# LiPo_Drop_Charger.net
KiCad netlist of a schematic drawn in EAGLE
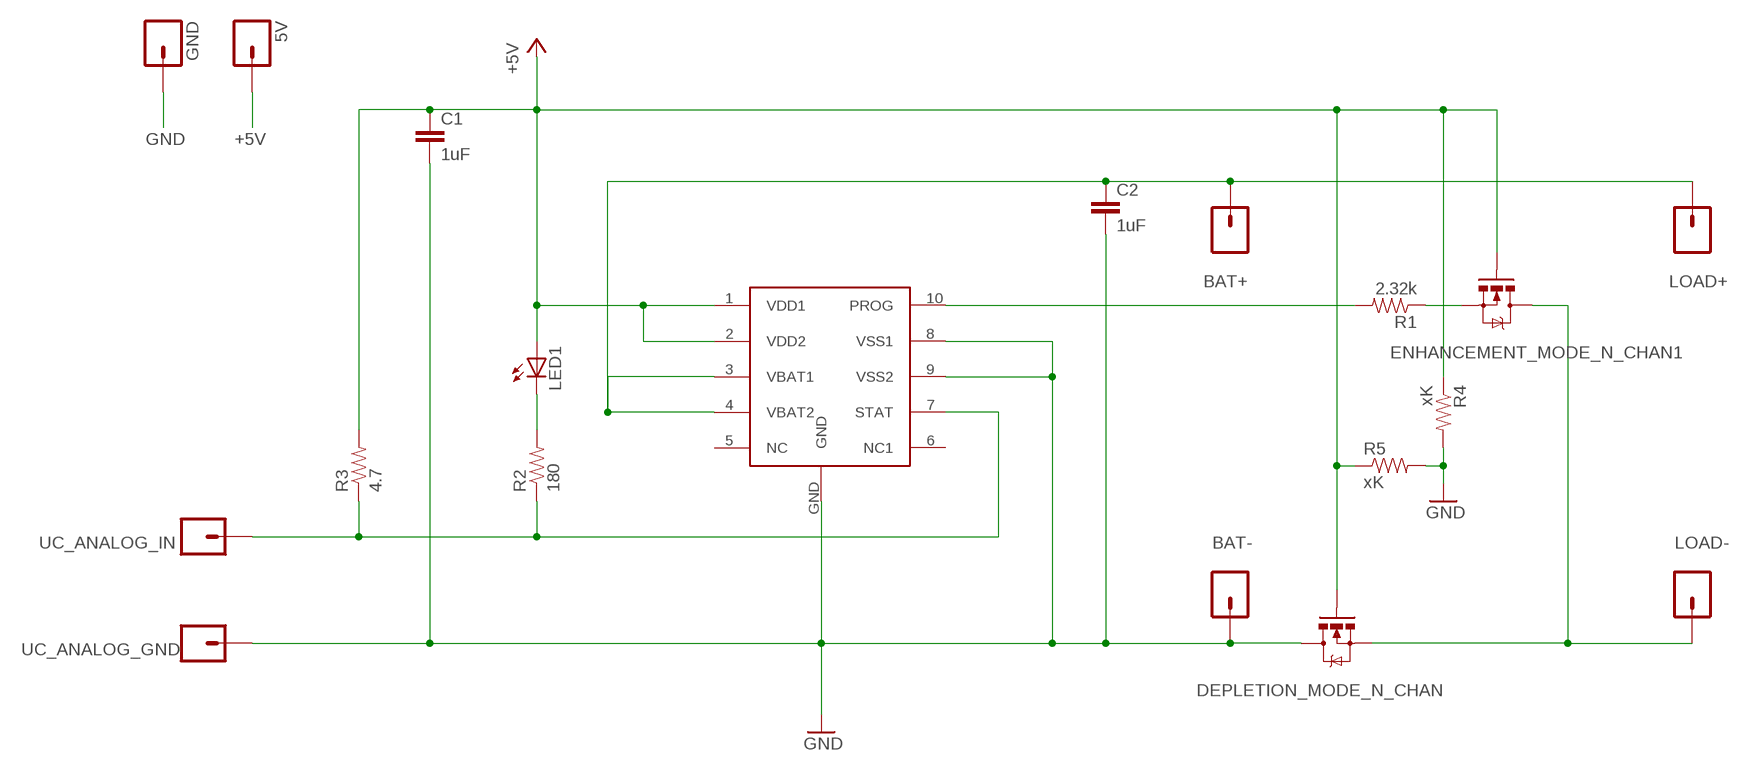
[diagram p0: schematic, sheet 1]

(export (version "E")
  (design (tool "Eeschema 10.0.6"))
  (components
    (comp (ref "5V")
      (value "M01PTH")
      (footprint "eagle-import:1X01")
      (libsource (lib "eagle-import") (part "M01PTH"))
    )
    (comp (ref "BAT+")
      (value "M01PTH")
      (footprint "eagle-import:1X01")
      (libsource (lib "eagle-import") (part "M01PTH"))
    )
    (comp (ref "BAT-")
      (value "M01PTH")
      (footprint "eagle-import:1X01")
      (libsource (lib "eagle-import") (part "M01PTH"))
    )
    (comp (ref "C1")
      (value "1uF")
      (footprint "eagle-import:0805")
      (libsource (lib "eagle-import") (part "CAP0805"))
    )
    (comp (ref "C2")
      (value "1uF")
      (footprint "eagle-import:0805")
      (libsource (lib "eagle-import") (part "CAP0805"))
    )
    (comp (ref "DEPLETION_MODE_N_CHAN")
      (value "MOSFET-NCHANNELSMD")
      (footprint "eagle-import:SOT23-3")
      (libsource (lib "eagle-import") (part "MOSFET-NCHANNELSMD"))
    )
    (comp (ref "ENHANCEMENT_MODE_N_CHAN1")
      (value "MOSFET-NCHANNELSMD")
      (footprint "eagle-import:SOT23-3")
      (libsource (lib "eagle-import") (part "MOSFET-NCHANNELSMD"))
    )
    (comp (ref "GND")
      (value "M01PTH")
      (footprint "eagle-import:1X01")
      (libsource (lib "eagle-import") (part "M01PTH"))
    )
    (comp (ref "LED1")
      (value "LED0603")
      (footprint "eagle-import:LED-0603")
      (libsource (lib "eagle-import") (part "LED0603"))
    )
    (comp (ref "LOAD+")
      (value "M01PTH")
      (footprint "eagle-import:1X01")
      (libsource (lib "eagle-import") (part "M01PTH"))
    )
    (comp (ref "LOAD-")
      (value "M01PTH")
      (footprint "eagle-import:1X01")
      (libsource (lib "eagle-import") (part "M01PTH"))
    )
    (comp (ref "R1")
      (value "2.32k")
      (footprint "eagle-import:0805")
      (libsource (lib "eagle-import") (part "RESISTOR0805-RES"))
    )
    (comp (ref "R2")
      (value "180")
      (footprint "eagle-import:0805")
      (libsource (lib "eagle-import") (part "RESISTOR0805-RES"))
    )
    (comp (ref "R3")
      (value "4.7")
      (footprint "eagle-import:0805")
      (libsource (lib "eagle-import") (part "RESISTOR0805-RES"))
    )
    (comp (ref "R4")
      (value "xK")
      (footprint "eagle-import:0805")
      (libsource (lib "eagle-import") (part "RESISTOR0805-RES"))
    )
    (comp (ref "R5")
      (value "xK")
      (footprint "eagle-import:0805")
      (libsource (lib "eagle-import") (part "RESISTOR0805-RES"))
    )
    (comp (ref "U$1")
      (value "MCP73213")
      (footprint "eagle-import:DFN10_3X3MM")
      (libsource (lib "eagle-import") (part "MCP73213"))
    )
    (comp (ref "UC_ANALOG_GND")
      (value "M01PTH")
      (footprint "eagle-import:1X01")
      (libsource (lib "eagle-import") (part "M01PTH"))
    )
    (comp (ref "UC_ANALOG_IN")
      (value "M01PTH")
      (footprint "eagle-import:1X01")
      (libsource (lib "eagle-import") (part "M01PTH"))
    )
  )
  (nets
    (net (code "1") (name "+5V") (class "Default")
      (node (ref "5V") (pin "1") (pinfunction "1_1") (pintype "passive"))
      (node (ref "C1") (pin "1") (pinfunction "1_1") (pintype "passive"))
      (node (ref "DEPLETION_MODE_N_CHAN") (pin "1") (pinfunction "G_1") (pintype "passive"))
      (node (ref "ENHANCEMENT_MODE_N_CHAN1") (pin "1") (pinfunction "G_1") (pintype "passive"))
      (node (ref "LED1") (pin "A") (pinfunction "A_A") (pintype "passive"))
      (node (ref "R3") (pin "2") (pinfunction "2_2") (pintype "passive"))
      (node (ref "R4") (pin "1") (pinfunction "1_1") (pintype "passive"))
      (node (ref "R5") (pin "1") (pinfunction "1_1") (pintype "passive"))
      (node (ref "U$1") (pin "1") (pinfunction "VDD1_1") (pintype "bidirectional"))
      (node (ref "U$1") (pin "2") (pinfunction "VDD2_2") (pintype "bidirectional"))
    )
    (net (code "2") (name "GND") (class "Default")
      (node (ref "BAT-") (pin "1") (pinfunction "1_1") (pintype "passive"))
      (node (ref "C1") (pin "2") (pinfunction "2_2") (pintype "passive"))
      (node (ref "C2") (pin "2") (pinfunction "2_2") (pintype "passive"))
      (node (ref "DEPLETION_MODE_N_CHAN") (pin "3") (pinfunction "D_3") (pintype "passive"))
      (node (ref "GND") (pin "1") (pinfunction "1_1") (pintype "passive"))
      (node (ref "R4") (pin "2") (pinfunction "2_2") (pintype "passive"))
      (node (ref "R5") (pin "2") (pinfunction "2_2") (pintype "passive"))
      (node (ref "U$1") (pin "8") (pinfunction "VSS1_8") (pintype "bidirectional"))
      (node (ref "U$1") (pin "9") (pinfunction "VSS2_9") (pintype "bidirectional"))
      (node (ref "U$1") (pin "GND") (pinfunction "GND_GND") (pintype "bidirectional"))
      (node (ref "UC_ANALOG_GND") (pin "1") (pinfunction "1_1") (pintype "passive"))
    )
    (net (code "3") (name "Net-(DEPLETION_MODE_N_CHAN-S)") (class "Default")
      (node (ref "DEPLETION_MODE_N_CHAN") (pin "2") (pinfunction "S_2") (pintype "passive"))
      (node (ref "ENHANCEMENT_MODE_N_CHAN1") (pin "3") (pinfunction "D_3") (pintype "passive"))
      (node (ref "LOAD-") (pin "1") (pinfunction "1_1") (pintype "passive"))
    )
    (net (code "4") (name "Net-(ENHANCEMENT_MODE_N_CHAN1-S)") (class "Default")
      (node (ref "ENHANCEMENT_MODE_N_CHAN1") (pin "2") (pinfunction "S_2") (pintype "passive"))
      (node (ref "R1") (pin "1") (pinfunction "1_1") (pintype "passive"))
    )
    (net (code "5") (name "Net-(LED1-PadC)") (class "Default")
      (node (ref "LED1") (pin "C") (pinfunction "C_C") (pintype "passive"))
      (node (ref "R2") (pin "2") (pinfunction "2_2") (pintype "passive"))
    )
    (net (code "6") (name "Net-(U$1-PROG)") (class "Default")
      (node (ref "R1") (pin "2") (pinfunction "2_2") (pintype "passive"))
      (node (ref "U$1") (pin "10") (pinfunction "PROG_10") (pintype "bidirectional"))
    )
    (net (code "7") (name "Net-(U$1-STAT)") (class "Default")
      (node (ref "R2") (pin "1") (pinfunction "1_1") (pintype "passive"))
      (node (ref "R3") (pin "1") (pinfunction "1_1") (pintype "passive"))
      (node (ref "U$1") (pin "7") (pinfunction "STAT_7") (pintype "bidirectional"))
      (node (ref "UC_ANALOG_IN") (pin "1") (pinfunction "1_1") (pintype "passive"))
    )
    (net (code "8") (name "Net-(U$1-VBAT1)") (class "Default")
      (node (ref "BAT+") (pin "1") (pinfunction "1_1") (pintype "passive"))
      (node (ref "C2") (pin "1") (pinfunction "1_1") (pintype "passive"))
      (node (ref "LOAD+") (pin "1") (pinfunction "1_1") (pintype "passive"))
      (node (ref "U$1") (pin "3") (pinfunction "VBAT1_3") (pintype "bidirectional"))
      (node (ref "U$1") (pin "4") (pinfunction "VBAT2_4") (pintype "bidirectional"))
    )
    (net (code "9") (name "unconnected-(U$1-NC-Pad5)") (class "Default")
      (node (ref "U$1") (pin "5") (pinfunction "NC_5") (pintype "bidirectional"))
    )
    (net (code "10") (name "unconnected-(U$1-NC1-Pad6)") (class "Default")
      (node (ref "U$1") (pin "6") (pinfunction "NC1_6") (pintype "bidirectional"))
    )
  )
)
